# KC_Input_VAS_Schematic.net
KiCad netlist of a schematic drawn in Altium Designer
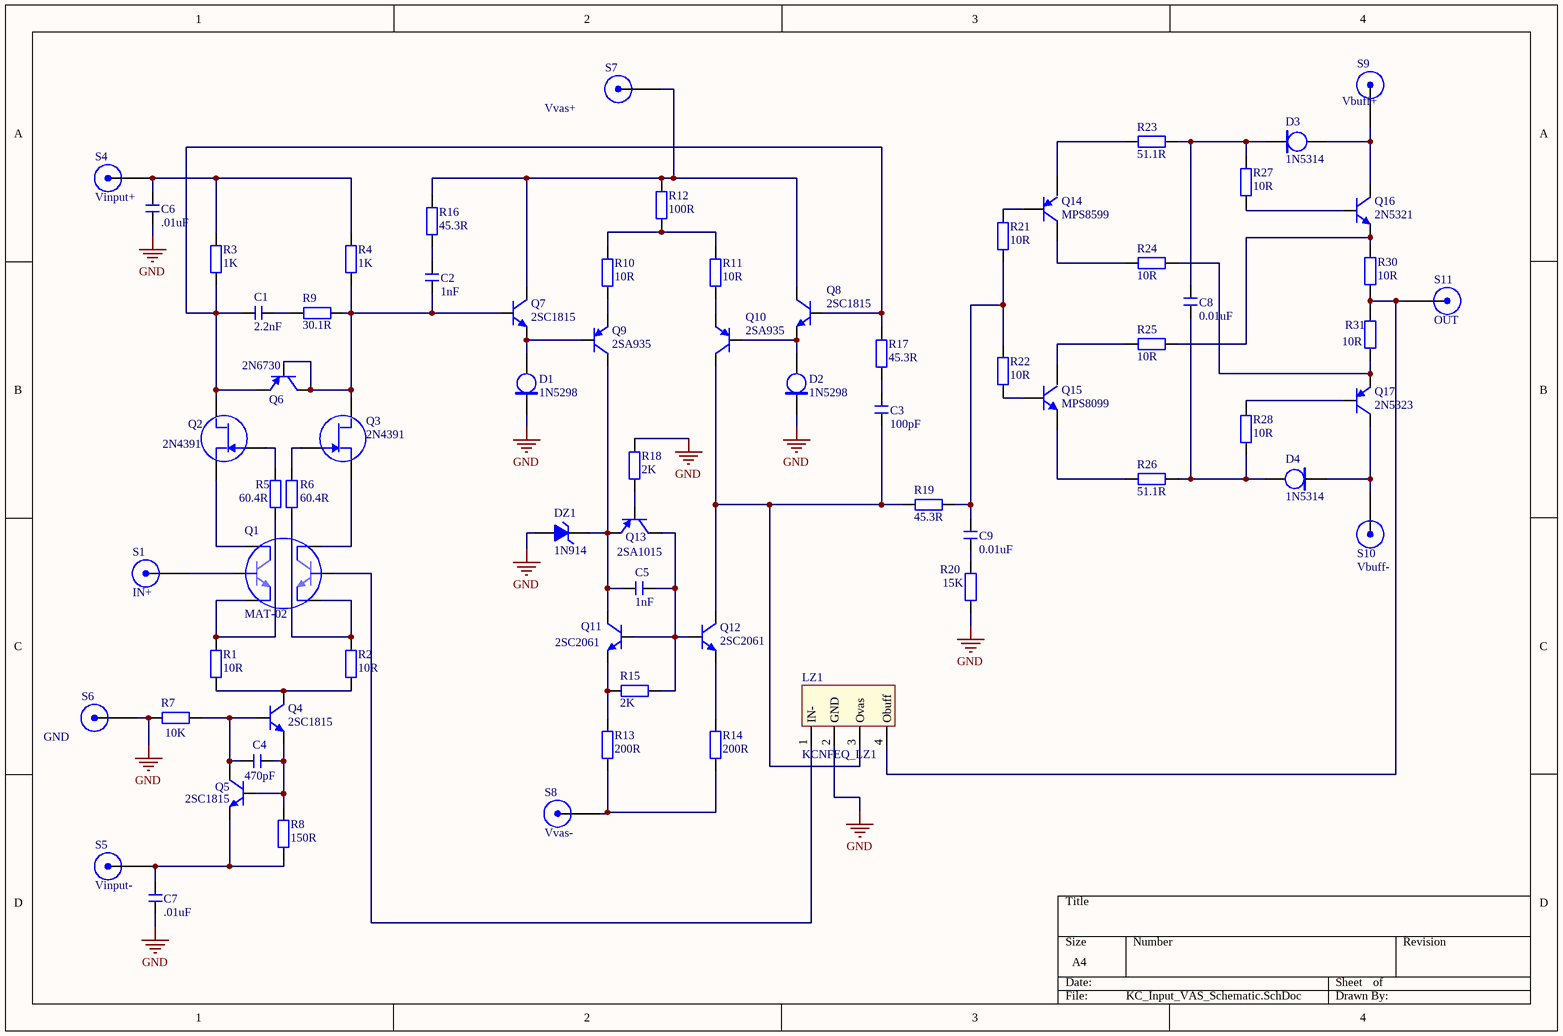
[diagram p0: KC_Input_VAS_Schematic.SchDoc]

(export (version "E")
  (design (tool "Eeschema 10.0.6"))
  (components
    (comp (ref "C1")
      (value "2.2nF")
      (footprint "CBB 6.3*6.3*5")
      (description "CBB电容")
      (fields (field (name "版权归属") "源创客"))
      (libsource (lib "电阻-电容-电感") (part "C-CBB"))
    )
    (comp (ref "C2")
      (value "1nF")
      (footprint "CBB 6.3*6.3*5")
      (description "CBB电容")
      (fields (field (name "版权归属") "源创客"))
      (libsource (lib "电阻-电容-电感") (part "C-CBB"))
    )
    (comp (ref "C3")
      (value "100pF")
      (footprint "CBB 6.3*6.3*5")
      (description "CBB电容")
      (fields (field (name "版权归属") "源创客"))
      (libsource (lib "电阻-电容-电感") (part "C-CBB"))
    )
    (comp (ref "C4")
      (value "470pF")
      (footprint "CBB 6.3*6.3*5")
      (description "CBB电容")
      (fields (field (name "版权归属") "源创客"))
      (libsource (lib "电阻-电容-电感") (part "C-CBB"))
    )
    (comp (ref "C5")
      (value "1nF")
      (footprint "CBB 6.3*6.3*5")
      (description "CBB电容")
      (fields (field (name "版权归属") "源创客"))
      (libsource (lib "电阻-电容-电感") (part "C-CBB"))
    )
    (comp (ref "C6")
      (value ".01uF")
      (footprint "CBB 6.3*6.3*5")
      (description "CBB电容")
      (fields (field (name "版权归属") "源创客"))
      (libsource (lib "电阻-电容-电感") (part "C-CBB"))
    )
    (comp (ref "C7")
      (value ".01uF")
      (footprint "CBB 6.3*6.3*5")
      (description "CBB电容")
      (fields (field (name "版权归属") "源创客"))
      (libsource (lib "电阻-电容-电感") (part "C-CBB"))
    )
    (comp (ref "C8")
      (value "0.01uF")
      (footprint "CBB 6.3*6.3*5")
      (description "CBB电容")
      (fields (field (name "版权归属") "源创客"))
      (libsource (lib "电阻-电容-电感") (part "C-CBB"))
    )
    (comp (ref "C9")
      (value "0.01uF")
      (footprint "CBB 6.3*6.3*5")
      (description "CBB电容")
      (fields (field (name "版权归属") "源创客"))
      (libsource (lib "电阻-电容-电感") (part "C-CBB"))
    )
    (comp (ref "D1")
      (value "1N5298")
      (footprint "DO-41")
      (description "Current Regulator Diodes")
      (libsource (lib "") (part "1N5xxx_1"))
    )
    (comp (ref "D2")
      (value "1N5298")
      (footprint "DO-41")
      (description "Current Regulator Diodes")
      (libsource (lib "") (part "1N5xxx_1"))
    )
    (comp (ref "D3")
      (value "1N5314")
      (footprint "DO-41G")
      (description "Current Regulator Diodes")
      (libsource (lib "二极管-整流桥") (part "1N5xxx"))
    )
    (comp (ref "D4")
      (value "1N5314")
      (footprint "DO-41G")
      (description "Current Regulator Diodes")
      (libsource (lib "二极管-整流桥") (part "1N5xxx"))
    )
    (comp (ref "DZ1")
      (value "1N914")
      (footprint "DO-41")
      (description "3V/0.5W稳压管")
      (fields (field (name "版权归属") "源创客"))
      (libsource (lib "二极管-整流桥") (part "1N4619"))
    )
    (comp (ref "LZ1")
      (value "KCNFEQ_LZ1")
      (footprint "LZ12-3.81")
      (description "King Cello Negative Feedback and EQ Board")
      (libsource (lib "KC_amp") (part "KCNFEQ_LZ1"))
    )
    (comp (ref "Q1")
      (value "MAT-02")
      (footprint "DIP-8")
      (description "孪生对管-NPN型 40V/20ma")
      (libsource (lib "三极管") (part "MAT-02"))
    )
    (comp (ref "Q2")
      (value "2N4391")
      (footprint "TO-18_SMALLHOLE")
      (description "N沟道JFET开关管 40V/150ma")
      (libsource (lib "场效应管") (part "2N4391"))
    )
    (comp (ref "Q3")
      (value "2N4391")
      (footprint "TO-18_SMALLHOLE")
      (description "N沟道JFET开关管 40V/150ma")
      (libsource (lib "场效应管") (part "2N4391"))
    )
    (comp (ref "Q4")
      (value "2SC1815")
      (footprint "TO92A_SmallHole")
      (description "音频放大-NPN型")
      (libsource (lib "三极管") (part "2SC1815"))
    )
    (comp (ref "Q5")
      (value "2SC1815")
      (footprint "TO92A_SmallHole")
      (description "音频放大-NPN型")
      (libsource (lib "三极管") (part "2SC1815"))
    )
    (comp (ref "Q6")
      (value "2N6730")
      (footprint "TO92A_SmallHole")
      (description "中功率放大-PNP型")
      (libsource (lib "三极管") (part "2N6728/6729/6730"))
    )
    (comp (ref "Q7")
      (value "2SC1815")
      (footprint "TO92A_SmallHole")
      (description "音频放大-NPN型")
      (libsource (lib "三极管") (part "2SC1815"))
    )
    (comp (ref "Q8")
      (value "2SC1815")
      (footprint "TO92A_SmallHole")
      (description "音频放大-NPN型")
      (libsource (lib "三极管") (part "2SC1815"))
    )
    (comp (ref "Q9")
      (value "2SA935")
      (footprint "TO92A_SmallHole")
      (description "音频功放-PNP型 50V/500ma")
      (libsource (lib "三极管") (part "2SA935"))
    )
    (comp (ref "Q10")
      (value "2SA935")
      (footprint "TO92A_SmallHole")
      (description "音频功放-PNP型 50V/500ma")
      (libsource (lib "三极管") (part "2SA935"))
    )
    (comp (ref "Q11")
      (value "2SC2061")
      (footprint "TO92A_SmallHole")
      (description "音频放大-NPN型 50V/500ma")
      (libsource (lib "三极管") (part "2SC2061"))
    )
    (comp (ref "Q12")
      (value "2SC2061")
      (footprint "TO92A_SmallHole")
      (description "音频放大-NPN型 50V/500ma")
      (libsource (lib "三极管") (part "2SC2061"))
    )
    (comp (ref "Q13")
      (value "2SA1015")
      (footprint "TO92A_SmallHole")
      (description "音频放大-PNP型")
      (libsource (lib "三极管") (part "2SA1015"))
    )
    (comp (ref "Q14")
      (value "MPS8599")
      (footprint "TO92A_SmallHole")
      (description "音频放大-PNP型")
      (libsource (lib "三极管") (part "MPS8598/8599"))
    )
    (comp (ref "Q15")
      (value "MPS8099")
      (footprint "TO92A_SmallHole")
      (description "音频放大-NPN型")
      (libsource (lib "三极管") (part "MPS8098/8099"))
    )
    (comp (ref "Q16")
      (value "2N5321")
      (footprint "TO39_SMALLHOLE")
      (description "中功率放大-NPN型 100V/1.2a")
      (libsource (lib "三极管") (part "2N5320/5321"))
    )
    (comp (ref "Q17")
      (value "2N5323")
      (footprint "TO39_SMALLHOLE")
      (description "中功率放大-PNP型 100V/1.2a")
      (libsource (lib "三极管") (part "2N5322/5323"))
    )
    (comp (ref "R1")
      (value "10R")
      (footprint "RS 1/2W-L")
      (description "直插色环电阻")
      (fields (field (name "版权归属") "源创客"))
      (libsource (lib "电阻-电容-电感") (part "R-CRR"))
    )
    (comp (ref "R2")
      (value "10R")
      (footprint "RS 1/2W-L")
      (description "直插色环电阻")
      (fields (field (name "版权归属") "源创客"))
      (libsource (lib "电阻-电容-电感") (part "R-CRR"))
    )
    (comp (ref "R3")
      (value "1K")
      (footprint "RS 1/2W-L")
      (description "直插色环电阻")
      (fields (field (name "版权归属") "源创客"))
      (libsource (lib "电阻-电容-电感") (part "R-CRR"))
    )
    (comp (ref "R4")
      (value "1K")
      (footprint "RS 1/2W-L")
      (description "直插色环电阻")
      (fields (field (name "版权归属") "源创客"))
      (libsource (lib "电阻-电容-电感") (part "R-CRR"))
    )
    (comp (ref "R5")
      (value "60.4R")
      (footprint "RS 1/2W-L")
      (description "直插色环电阻")
      (fields (field (name "版权归属") "源创客"))
      (libsource (lib "电阻-电容-电感") (part "R-CRR"))
    )
    (comp (ref "R6")
      (value "60.4R")
      (footprint "RS 1/2W-L")
      (description "直插色环电阻")
      (fields (field (name "版权归属") "源创客"))
      (libsource (lib "电阻-电容-电感") (part "R-CRR"))
    )
    (comp (ref "R7")
      (value "10K")
      (footprint "RS 1/2W-L")
      (description "直插色环电阻")
      (fields (field (name "版权归属") "源创客"))
      (libsource (lib "电阻-电容-电感") (part "R-CRR"))
    )
    (comp (ref "R8")
      (value "150R")
      (footprint "RS 1/2W-L")
      (description "直插色环电阻")
      (fields (field (name "版权归属") "源创客"))
      (libsource (lib "电阻-电容-电感") (part "R-CRR"))
    )
    (comp (ref "R9")
      (value "30.1R")
      (footprint "RS 1/2W-L")
      (description "直插色环电阻")
      (fields (field (name "版权归属") "源创客"))
      (libsource (lib "电阻-电容-电感") (part "R-CRR"))
    )
    (comp (ref "R10")
      (value "10R")
      (footprint "RS 1/2W-L")
      (description "直插色环电阻")
      (fields (field (name "版权归属") "源创客"))
      (libsource (lib "电阻-电容-电感") (part "R-CRR"))
    )
    (comp (ref "R11")
      (value "10R")
      (footprint "RS 1/2W-L")
      (description "直插色环电阻")
      (fields (field (name "版权归属") "源创客"))
      (libsource (lib "电阻-电容-电感") (part "R-CRR"))
    )
    (comp (ref "R12")
      (value "100R")
      (footprint "RS 1/2W-L")
      (description "直插色环电阻")
      (fields (field (name "版权归属") "源创客"))
      (libsource (lib "电阻-电容-电感") (part "R-CRR"))
    )
    (comp (ref "R13")
      (value "200R")
      (footprint "RS 1/2W-L")
      (description "直插色环电阻")
      (fields (field (name "版权归属") "源创客"))
      (libsource (lib "电阻-电容-电感") (part "R-CRR"))
    )
    (comp (ref "R14")
      (value "200R")
      (footprint "RS 1/2W-L")
      (description "直插色环电阻")
      (fields (field (name "版权归属") "源创客"))
      (libsource (lib "电阻-电容-电感") (part "R-CRR"))
    )
    (comp (ref "R15")
      (value "2K")
      (footprint "RS 1/2W-L")
      (description "直插色环电阻")
      (fields (field (name "版权归属") "源创客"))
      (libsource (lib "电阻-电容-电感") (part "R-CRR"))
    )
    (comp (ref "R16")
      (value "45.3R")
      (footprint "RS 1/2W-L")
      (description "直插色环电阻")
      (fields (field (name "版权归属") "源创客"))
      (libsource (lib "电阻-电容-电感") (part "R-CRR"))
    )
    (comp (ref "R17")
      (value "45.3R")
      (footprint "RS 1/2W-L")
      (description "直插色环电阻")
      (fields (field (name "版权归属") "源创客"))
      (libsource (lib "电阻-电容-电感") (part "R-CRR"))
    )
    (comp (ref "R18")
      (value "2K")
      (footprint "RS 1/2W-L")
      (description "直插色环电阻")
      (fields (field (name "版权归属") "源创客"))
      (libsource (lib "电阻-电容-电感") (part "R-CRR"))
    )
    (comp (ref "R19")
      (value "45.3R")
      (footprint "RS 1/2W-L")
      (description "直插色环电阻")
      (fields (field (name "版权归属") "源创客"))
      (libsource (lib "电阻-电容-电感") (part "R-CRR"))
    )
    (comp (ref "R20")
      (value "15K")
      (footprint "RS 1/2W-L")
      (description "直插色环电阻")
      (fields (field (name "版权归属") "源创客"))
      (libsource (lib "电阻-电容-电感") (part "R-CRR"))
    )
    (comp (ref "R21")
      (value "10R")
      (footprint "RS 1/2W-L")
      (description "直插色环电阻")
      (fields (field (name "版权归属") "源创客"))
      (libsource (lib "电阻-电容-电感") (part "R-CRR"))
    )
    (comp (ref "R22")
      (value "10R")
      (footprint "RS 1/2W-L")
      (description "直插色环电阻")
      (fields (field (name "版权归属") "源创客"))
      (libsource (lib "电阻-电容-电感") (part "R-CRR"))
    )
    (comp (ref "R23")
      (value "51.1R")
      (footprint "RS 1/2W-L")
      (description "直插色环电阻")
      (fields (field (name "版权归属") "源创客"))
      (libsource (lib "电阻-电容-电感") (part "R-CRR"))
    )
    (comp (ref "R24")
      (value "10R")
      (footprint "RS 1/2W-L")
      (description "直插色环电阻")
      (fields (field (name "版权归属") "源创客"))
      (libsource (lib "电阻-电容-电感") (part "R-CRR"))
    )
    (comp (ref "R25")
      (value "10R")
      (footprint "RS 1/2W-L")
      (description "直插色环电阻")
      (fields (field (name "版权归属") "源创客"))
      (libsource (lib "电阻-电容-电感") (part "R-CRR"))
    )
    (comp (ref "R26")
      (value "51.1R")
      (footprint "RS 1/2W-L")
      (description "直插色环电阻")
      (fields (field (name "版权归属") "源创客"))
      (libsource (lib "电阻-电容-电感") (part "R-CRR"))
    )
    (comp (ref "R27")
      (value "10R")
      (footprint "RS 1/2W-L")
      (description "直插色环电阻")
      (fields (field (name "版权归属") "源创客"))
      (libsource (lib "电阻-电容-电感") (part "R-CRR"))
    )
    (comp (ref "R28")
      (value "10R")
      (footprint "RS 1/2W-L")
      (description "直插色环电阻")
      (fields (field (name "版权归属") "源创客"))
      (libsource (lib "电阻-电容-电感") (part "R-CRR"))
    )
    (comp (ref "R30")
      (value "10R")
      (footprint "RS 2W")
      (description "直插色环电阻")
      (fields (field (name "版权归属") "源创客"))
      (libsource (lib "电阻-电容-电感") (part "R-CRR"))
    )
    (comp (ref "R31")
      (value "10R")
      (footprint "RS 2W")
      (description "直插色环电阻")
      (fields (field (name "版权归属") "源创客"))
      (libsource (lib "电阻-电容-电感") (part "R-CRR"))
    )
    (comp (ref "S1")
      (value "IN+")
      (footprint "Screw-M2-s")
      (description "Screw Connector")
      (libsource (lib "Connectors") (part "ScrewConnector"))
    )
    (comp (ref "S4")
      (value "Vinput+")
      (footprint "Screw-M2-s")
      (description "Screw Connector")
      (libsource (lib "Connectors") (part "ScrewConnector"))
    )
    (comp (ref "S5")
      (value "Vinput-")
      (footprint "Screw-M2-s")
      (description "Screw Connector")
      (libsource (lib "Connectors") (part "ScrewConnector"))
    )
    (comp (ref "S6")
      (value "GND")
      (footprint "Screw-M2-s")
      (description "Screw Connector")
      (libsource (lib "Connectors") (part "ScrewConnector"))
    )
    (comp (ref "S7")
      (value "Vvas+")
      (footprint "Screw-M2-s")
      (description "Screw Connector")
      (libsource (lib "Connectors") (part "ScrewConnector"))
    )
    (comp (ref "S8")
      (value "Vvas-")
      (footprint "Screw-M2-s")
      (description "Screw Connector")
      (libsource (lib "Connectors") (part "ScrewConnector"))
    )
    (comp (ref "S9")
      (value "Vbuff+")
      (footprint "Screw-M2-s")
      (description "Screw Connector")
      (libsource (lib "Connectors") (part "ScrewConnector"))
    )
    (comp (ref "S10")
      (value "Vbuff-")
      (footprint "Screw-M2-s")
      (description "Screw Connector")
      (libsource (lib "Connectors") (part "ScrewConnector"))
    )
    (comp (ref "S11")
      (value "OUT")
      (footprint "Screw-M2-s")
      (description "Screw Connector")
      (libsource (lib "Connectors") (part "ScrewConnector"))
    )
  )
  (nets
    (net (code "1") (name "GND") (class "Default")
      (node (ref "C6") (pin "2") (pinfunction "2_2") (pintype "passive"))
      (node (ref "C7") (pin "1") (pinfunction "1_1") (pintype "passive"))
      (node (ref "D1") (pin "2") (pinfunction "Anode_2") (pintype "passive"))
      (node (ref "D2") (pin "2") (pinfunction "Anode_2") (pintype "passive"))
      (node (ref "DZ1") (pin "1") (pinfunction "A_1") (pintype "passive"))
      (node (ref "LZ1") (pin "2") (pinfunction "GND_2") (pintype "passive"))
      (node (ref "R18") (pin "2") (pinfunction "2_2") (pintype "passive"))
      (node (ref "R20") (pin "1") (pinfunction "1_1") (pintype "passive"))
      (node (ref "R7") (pin "1") (pinfunction "1_1") (pintype "passive"))
      (node (ref "S6") (pin "1") (pinfunction "X_1") (pintype "passive"))
    )
    (net (code "2") (name "Net-(C1-Pad2)") (class "Default")
      (node (ref "C1") (pin "2") (pinfunction "2_2") (pintype "passive"))
      (node (ref "R9") (pin "1") (pinfunction "1_1") (pintype "passive"))
    )
    (net (code "3") (name "Net-(C2-Pad1)") (class "Default")
      (node (ref "C2") (pin "1") (pinfunction "1_1") (pintype "passive"))
      (node (ref "R16") (pin "1") (pinfunction "1_1") (pintype "passive"))
    )
    (net (code "4") (name "Net-(C3-Pad2)") (class "Default")
      (node (ref "C3") (pin "2") (pinfunction "2_2") (pintype "passive"))
      (node (ref "R17") (pin "1") (pinfunction "1_1") (pintype "passive"))
    )
    (net (code "5") (name "Net-(C9-Pad1)") (class "Default")
      (node (ref "C9") (pin "1") (pinfunction "1_1") (pintype "passive"))
      (node (ref "R19") (pin "2") (pinfunction "2_2") (pintype "passive"))
      (node (ref "R21") (pin "1") (pinfunction "1_1") (pintype "passive"))
      (node (ref "R22") (pin "2") (pinfunction "2_2") (pintype "passive"))
    )
    (net (code "6") (name "Net-(C9-Pad2)") (class "Default")
      (node (ref "C9") (pin "2") (pinfunction "2_2") (pintype "passive"))
      (node (ref "R20") (pin "2") (pinfunction "2_2") (pintype "passive"))
    )
    (net (code "7") (name "Net-(D1-Cathode)") (class "Default")
      (node (ref "D1") (pin "1") (pinfunction "Cathode_1") (pintype "passive"))
      (node (ref "Q7") (pin "1") (pinfunction "E_1") (pintype "passive"))
      (node (ref "Q9") (pin "3") (pinfunction "B_3") (pintype "passive"))
    )
    (net (code "8") (name "Net-(D2-Cathode)") (class "Default")
      (node (ref "D2") (pin "1") (pinfunction "Cathode_1") (pintype "passive"))
      (node (ref "Q10") (pin "3") (pinfunction "B_3") (pintype "passive"))
      (node (ref "Q8") (pin "1") (pinfunction "E_1") (pintype "passive"))
    )
    (net (code "9") (name "Net-(D3-Anode)") (class "Default")
      (node (ref "D3") (pin "2") (pinfunction "Anode_2") (pintype "passive"))
      (node (ref "Q16") (pin "2") (pinfunction "C_2") (pintype "passive"))
      (node (ref "S9") (pin "1") (pinfunction "X_1") (pintype "passive"))
    )
    (net (code "10") (name "Net-(D3-Cathode)") (class "Default")
      (node (ref "C8") (pin "2") (pinfunction "2_2") (pintype "passive"))
      (node (ref "D3") (pin "1") (pinfunction "Cathode_1") (pintype "passive"))
      (node (ref "R23") (pin "1") (pinfunction "1_1") (pintype "passive"))
      (node (ref "R27") (pin "2") (pinfunction "2_2") (pintype "passive"))
    )
    (net (code "11") (name "Net-(D4-Anode)") (class "Default")
      (node (ref "C8") (pin "1") (pinfunction "1_1") (pintype "passive"))
      (node (ref "D4") (pin "2") (pinfunction "Anode_2") (pintype "passive"))
      (node (ref "R26") (pin "1") (pinfunction "1_1") (pintype "passive"))
      (node (ref "R28") (pin "1") (pinfunction "1_1") (pintype "passive"))
    )
    (net (code "12") (name "Net-(D4-Cathode)") (class "Default")
      (node (ref "D4") (pin "1") (pinfunction "Cathode_1") (pintype "passive"))
      (node (ref "Q17") (pin "2") (pinfunction "C_2") (pintype "passive"))
      (node (ref "S10") (pin "1") (pinfunction "X_1") (pintype "passive"))
    )
    (net (code "13") (name "Net-(DZ1-K)") (class "Default")
      (node (ref "C5") (pin "1") (pinfunction "1_1") (pintype "passive"))
      (node (ref "DZ1") (pin "2") (pinfunction "K_2") (pintype "passive"))
      (node (ref "Q11") (pin "2") (pinfunction "C_2") (pintype "passive"))
      (node (ref "Q13") (pin "1") (pinfunction "E_1") (pintype "passive"))
      (node (ref "Q9") (pin "2") (pinfunction "C_2") (pintype "passive"))
    )
    (net (code "14") (name "Net-(LZ1-IN-)") (class "Default")
      (node (ref "LZ1") (pin "1") (pinfunction "IN-_1") (pintype "passive"))
      (node (ref "Q1") (pin "6") (pinfunction "B_6") (pintype "passive"))
    )
    (net (code "15") (name "Net-(LZ1-Obuff)") (class "Default")
      (node (ref "LZ1") (pin "4") (pinfunction "Obuff_4") (pintype "passive"))
      (node (ref "R30") (pin "1") (pinfunction "1_1") (pintype "passive"))
      (node (ref "R31") (pin "2") (pinfunction "2_2") (pintype "passive"))
      (node (ref "S11") (pin "1") (pinfunction "X_1") (pintype "passive"))
    )
    (net (code "16") (name "Net-(LZ1-Ovas)") (class "Default")
      (node (ref "C3") (pin "1") (pinfunction "1_1") (pintype "passive"))
      (node (ref "LZ1") (pin "3") (pinfunction "Ovas_3") (pintype "passive"))
      (node (ref "Q10") (pin "2") (pinfunction "C_2") (pintype "passive"))
      (node (ref "Q12") (pin "2") (pinfunction "C_2") (pintype "passive"))
      (node (ref "R19") (pin "1") (pinfunction "1_1") (pintype "passive"))
    )
    (net (code "17") (name "Net-(Q1-E-Pad3)") (class "Default")
      (node (ref "Q1") (pin "3") (pinfunction "E_3") (pintype "passive"))
      (node (ref "R1") (pin "2") (pinfunction "2_2") (pintype "passive"))
      (node (ref "R5") (pin "1") (pinfunction "1_1") (pintype "passive"))
    )
    (net (code "18") (name "Net-(Q1-E-Pad5)") (class "Default")
      (node (ref "Q1") (pin "5") (pinfunction "E_5") (pintype "passive"))
      (node (ref "R2") (pin "2") (pinfunction "2_2") (pintype "passive"))
      (node (ref "R6") (pin "1") (pinfunction "1_1") (pintype "passive"))
    )
    (net (code "19") (name "Net-(Q2-D)") (class "Default")
      (node (ref "C1") (pin "1") (pinfunction "1_1") (pintype "passive"))
      (node (ref "Q2") (pin "3") (pinfunction "D_3") (pintype "passive"))
      (node (ref "Q6") (pin "1") (pinfunction "E_1") (pintype "passive"))
      (node (ref "Q8") (pin "3") (pinfunction "B_3") (pintype "passive"))
      (node (ref "R17") (pin "2") (pinfunction "2_2") (pintype "passive"))
      (node (ref "R3") (pin "1") (pinfunction "1_1") (pintype "passive"))
    )
    (net (code "20") (name "Net-(Q2-G)") (class "Default")
      (node (ref "Q2") (pin "2") (pinfunction "G_2") (pintype "passive"))
      (node (ref "R5") (pin "2") (pinfunction "2_2") (pintype "passive"))
    )
    (net (code "21") (name "Net-(Q2-S)") (class "Default")
      (node (ref "Q1") (pin "1") (pinfunction "C_1") (pintype "passive"))
      (node (ref "Q2") (pin "1") (pinfunction "S_1") (pintype "passive"))
    )
    (net (code "22") (name "Net-(Q3-D)") (class "Default")
      (node (ref "C2") (pin "2") (pinfunction "2_2") (pintype "passive"))
      (node (ref "Q3") (pin "3") (pinfunction "D_3") (pintype "passive"))
      (node (ref "Q6") (pin "2") (pinfunction "C_2") (pintype "passive"))
      (node (ref "Q6") (pin "3") (pinfunction "B_3") (pintype "passive"))
      (node (ref "Q7") (pin "3") (pinfunction "B_3") (pintype "passive"))
      (node (ref "R4") (pin "1") (pinfunction "1_1") (pintype "passive"))
      (node (ref "R9") (pin "2") (pinfunction "2_2") (pintype "passive"))
    )
    (net (code "23") (name "Net-(Q3-G)") (class "Default")
      (node (ref "Q3") (pin "2") (pinfunction "G_2") (pintype "passive"))
      (node (ref "R6") (pin "2") (pinfunction "2_2") (pintype "passive"))
    )
    (net (code "24") (name "Net-(Q3-S)") (class "Default")
      (node (ref "Q1") (pin "7") (pinfunction "C_7") (pintype "passive"))
      (node (ref "Q3") (pin "1") (pinfunction "S_1") (pintype "passive"))
    )
    (net (code "25") (name "Net-(Q4-B)") (class "Default")
      (node (ref "C4") (pin "1") (pinfunction "1_1") (pintype "passive"))
      (node (ref "Q4") (pin "3") (pinfunction "B_3") (pintype "passive"))
      (node (ref "Q5") (pin "2") (pinfunction "C_2") (pintype "passive"))
      (node (ref "R7") (pin "2") (pinfunction "2_2") (pintype "passive"))
    )
    (net (code "26") (name "Net-(Q4-C)") (class "Default")
      (node (ref "Q4") (pin "2") (pinfunction "C_2") (pintype "passive"))
      (node (ref "R1") (pin "1") (pinfunction "1_1") (pintype "passive"))
      (node (ref "R2") (pin "1") (pinfunction "1_1") (pintype "passive"))
    )
    (net (code "27") (name "Net-(Q4-E)") (class "Default")
      (node (ref "C4") (pin "2") (pinfunction "2_2") (pintype "passive"))
      (node (ref "Q4") (pin "1") (pinfunction "E_1") (pintype "passive"))
      (node (ref "Q5") (pin "3") (pinfunction "B_3") (pintype "passive"))
      (node (ref "R8") (pin "1") (pinfunction "1_1") (pintype "passive"))
    )
    (net (code "28") (name "Net-(Q5-E)") (class "Default")
      (node (ref "C7") (pin "2") (pinfunction "2_2") (pintype "passive"))
      (node (ref "Q5") (pin "1") (pinfunction "E_1") (pintype "passive"))
      (node (ref "R8") (pin "2") (pinfunction "2_2") (pintype "passive"))
      (node (ref "S5") (pin "1") (pinfunction "X_1") (pintype "passive"))
    )
    (net (code "29") (name "Net-(Q7-C)") (class "Default")
      (node (ref "Q7") (pin "2") (pinfunction "C_2") (pintype "passive"))
      (node (ref "Q8") (pin "2") (pinfunction "C_2") (pintype "passive"))
      (node (ref "R12") (pin "2") (pinfunction "2_2") (pintype "passive"))
      (node (ref "R16") (pin "2") (pinfunction "2_2") (pintype "passive"))
      (node (ref "S7") (pin "1") (pinfunction "X_1") (pintype "passive"))
    )
    (net (code "30") (name "Net-(Q9-E)") (class "Default")
      (node (ref "Q9") (pin "1") (pinfunction "E_1") (pintype "passive"))
      (node (ref "R10") (pin "1") (pinfunction "1_1") (pintype "passive"))
    )
    (net (code "31") (name "Net-(Q10-E)") (class "Default")
      (node (ref "Q10") (pin "1") (pinfunction "E_1") (pintype "passive"))
      (node (ref "R11") (pin "1") (pinfunction "1_1") (pintype "passive"))
    )
    (net (code "32") (name "Net-(Q11-B)") (class "Default")
      (node (ref "C5") (pin "2") (pinfunction "2_2") (pintype "passive"))
      (node (ref "Q11") (pin "3") (pinfunction "B_3") (pintype "passive"))
      (node (ref "Q12") (pin "3") (pinfunction "B_3") (pintype "passive"))
      (node (ref "Q13") (pin "2") (pinfunction "C_2") (pintype "passive"))
      (node (ref "R15") (pin "1") (pinfunction "1_1") (pintype "passive"))
    )
    (net (code "33") (name "Net-(Q11-E)") (class "Default")
      (node (ref "Q11") (pin "1") (pinfunction "E_1") (pintype "passive"))
      (node (ref "R13") (pin "2") (pinfunction "2_2") (pintype "passive"))
      (node (ref "R15") (pin "2") (pinfunction "2_2") (pintype "passive"))
    )
    (net (code "34") (name "Net-(Q12-E)") (class "Default")
      (node (ref "Q12") (pin "1") (pinfunction "E_1") (pintype "passive"))
      (node (ref "R14") (pin "2") (pinfunction "2_2") (pintype "passive"))
    )
    (net (code "35") (name "Net-(Q13-B)") (class "Default")
      (node (ref "Q13") (pin "3") (pinfunction "B_3") (pintype "passive"))
      (node (ref "R18") (pin "1") (pinfunction "1_1") (pintype "passive"))
    )
    (net (code "36") (name "Net-(Q14-B)") (class "Default")
      (node (ref "Q14") (pin "1") (pinfunction "B_1") (pintype "passive"))
      (node (ref "R21") (pin "2") (pinfunction "2_2") (pintype "passive"))
    )
    (net (code "37") (name "Net-(Q14-C)") (class "Default")
      (node (ref "Q14") (pin "2") (pinfunction "C_2") (pintype "passive"))
      (node (ref "R24") (pin "1") (pinfunction "1_1") (pintype "passive"))
    )
    (net (code "38") (name "Net-(Q14-E)") (class "Default")
      (node (ref "Q14") (pin "3") (pinfunction "E_3") (pintype "passive"))
      (node (ref "R23") (pin "2") (pinfunction "2_2") (pintype "passive"))
    )
    (net (code "39") (name "Net-(Q15-B)") (class "Default")
      (node (ref "Q15") (pin "1") (pinfunction "B_1") (pintype "passive"))
      (node (ref "R22") (pin "1") (pinfunction "1_1") (pintype "passive"))
    )
    (net (code "40") (name "Net-(Q15-C)") (class "Default")
      (node (ref "Q15") (pin "2") (pinfunction "C_2") (pintype "passive"))
      (node (ref "R25") (pin "1") (pinfunction "1_1") (pintype "passive"))
    )
    (net (code "41") (name "Net-(Q15-E)") (class "Default")
      (node (ref "Q15") (pin "3") (pinfunction "E_3") (pintype "passive"))
      (node (ref "R26") (pin "2") (pinfunction "2_2") (pintype "passive"))
    )
    (net (code "42") (name "Net-(Q16-B)") (class "Default")
      (node (ref "Q16") (pin "3") (pinfunction "B_3") (pintype "passive"))
      (node (ref "R27") (pin "1") (pinfunction "1_1") (pintype "passive"))
    )
    (net (code "43") (name "Net-(Q16-E)") (class "Default")
      (node (ref "Q16") (pin "1") (pinfunction "E_1") (pintype "passive"))
      (node (ref "R25") (pin "2") (pinfunction "2_2") (pintype "passive"))
      (node (ref "R30") (pin "2") (pinfunction "2_2") (pintype "passive"))
    )
    (net (code "44") (name "Net-(Q17-B)") (class "Default")
      (node (ref "Q17") (pin "3") (pinfunction "B_3") (pintype "passive"))
      (node (ref "R28") (pin "2") (pinfunction "2_2") (pintype "passive"))
    )
    (net (code "45") (name "Net-(Q17-E)") (class "Default")
      (node (ref "Q17") (pin "1") (pinfunction "E_1") (pintype "passive"))
      (node (ref "R24") (pin "2") (pinfunction "2_2") (pintype "passive"))
      (node (ref "R31") (pin "1") (pinfunction "1_1") (pintype "passive"))
    )
    (net (code "46") (name "Net-(R10-Pad2)") (class "Default")
      (node (ref "R10") (pin "2") (pinfunction "2_2") (pintype "passive"))
      (node (ref "R11") (pin "2") (pinfunction "2_2") (pintype "passive"))
      (node (ref "R12") (pin "1") (pinfunction "1_1") (pintype "passive"))
    )
    (net (code "47") (name "Net-(S1-X)") (class "Default")
      (node (ref "Q1") (pin "2") (pinfunction "B_2") (pintype "passive"))
      (node (ref "S1") (pin "1") (pinfunction "X_1") (pintype "passive"))
    )
    (net (code "48") (name "Net-(S4-X)") (class "Default")
      (node (ref "C6") (pin "1") (pinfunction "1_1") (pintype "passive"))
      (node (ref "R3") (pin "2") (pinfunction "2_2") (pintype "passive"))
      (node (ref "R4") (pin "2") (pinfunction "2_2") (pintype "passive"))
      (node (ref "S4") (pin "1") (pinfunction "X_1") (pintype "passive"))
    )
    (net (code "49") (name "Net-(S8-X)") (class "Default")
      (node (ref "R13") (pin "1") (pinfunction "1_1") (pintype "passive"))
      (node (ref "R14") (pin "1") (pinfunction "1_1") (pintype "passive"))
      (node (ref "S8") (pin "1") (pinfunction "X_1") (pintype "passive"))
    )
  )
)
